# VarmoEmergencyStop_-_Rev_A2.net
KiCad netlist of a schematic drawn in EAGLE
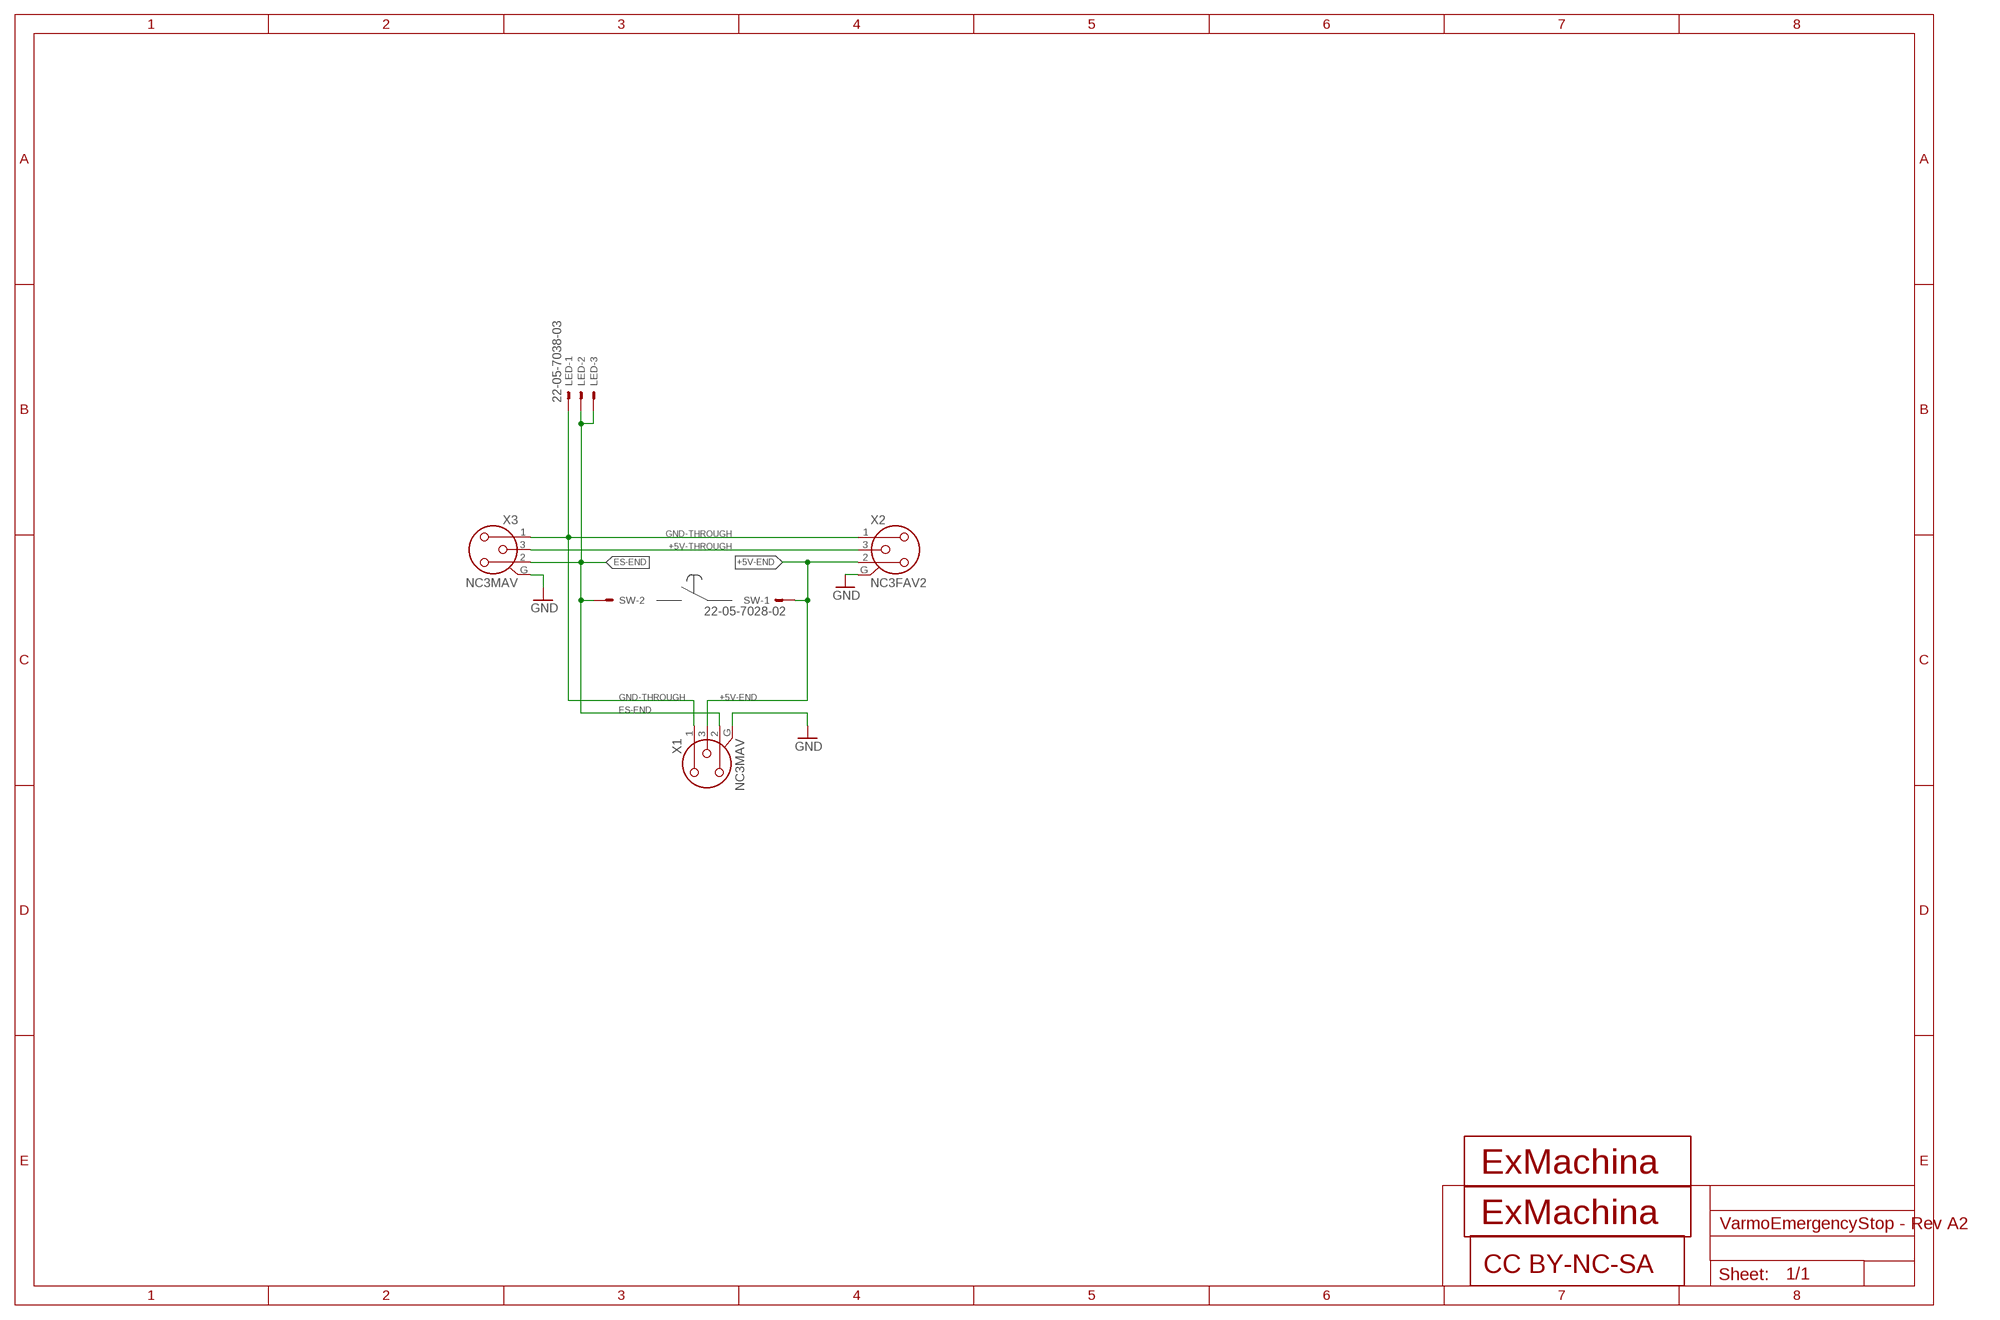
[diagram p0: schematic, sheet 1]

(export (version "E")
  (design (tool "Eeschema 10.0.6"))
  (components
    (comp (ref "LED")
      (value "22-05-7038-03")
      (footprint "eagle-import:7395-03")
      (libsource (lib "eagle-import") (part "22-?-0305-7038"))
    )
    (comp (ref "SW")
      (value "22-05-7028-02")
      (footprint "eagle-import:7395-02")
      (libsource (lib "eagle-import") (part "22-?-0205-7028"))
    )
    (comp (ref "U$1")
      (value "EXMACHINA-LOGO-NAME")
      (footprint "eagle-import:EXM-LOGO-BASELINE")
      (libsource (lib "eagle-import") (part "EXMACHINA-LOGO-NAME"))
    )
    (comp (ref "U$2")
      (value "CC-BY-NC-SA")
      (footprint "eagle-import:CC-BY-NC-SA")
      (libsource (lib "eagle-import") (part "CC-BY-NC-SA"))
    )
    (comp (ref "U$3")
      (value "EXMACHINA-LOGO-NAME")
      (footprint "eagle-import:EXM-LOGO-BASELINE")
      (libsource (lib "eagle-import") (part "EXMACHINA-LOGO-NAME"))
    )
    (comp (ref "X1")
      (value "NC3MAV")
      (footprint "eagle-import:NC3MAV")
      (fields (field (name "MF") "FARNELL"))
      (libsource (lib "eagle-import") (part "NC3MAV"))
    )
    (comp (ref "X2")
      (value "NC3FAV2")
      (footprint "eagle-import:NC3FAV2")
      (fields (field (name "MF") "NEUTRIK"))
      (libsource (lib "eagle-import") (part "NC3FAV2"))
    )
    (comp (ref "X3")
      (value "NC3MAV")
      (footprint "eagle-import:NC3MAV")
      (fields (field (name "MF") "FARNELL"))
      (libsource (lib "eagle-import") (part "NC3MAV"))
    )
  )
  (nets
    (net (code "1") (name "+5V-END") (class "Default")
      (node (ref "SW") (pin "1") (pinfunction "S_1") (pintype "passive"))
      (node (ref "X1") (pin "3") (pinfunction "3_3") (pintype "passive"))
      (node (ref "X2") (pin "2") (pinfunction "2_2") (pintype "passive"))
    )
    (net (code "2") (name "/+5V-THROUGH") (class "Default")
      (node (ref "X2") (pin "3") (pinfunction "3_3") (pintype "passive"))
      (node (ref "X3") (pin "3") (pinfunction "3_3") (pintype "passive"))
    )
    (net (code "3") (name "/GND-THROUGH") (class "Default")
      (node (ref "LED") (pin "1") (pinfunction "S_1") (pintype "passive"))
      (node (ref "X1") (pin "1") (pinfunction "1_1") (pintype "passive"))
      (node (ref "X2") (pin "1") (pinfunction "1_1") (pintype "passive"))
      (node (ref "X3") (pin "1") (pinfunction "1_1") (pintype "passive"))
    )
    (net (code "4") (name "ES-END") (class "Default")
      (node (ref "LED") (pin "2") (pinfunction "S_2") (pintype "passive"))
      (node (ref "LED") (pin "3") (pinfunction "S_3") (pintype "passive"))
      (node (ref "SW") (pin "2") (pinfunction "S_2") (pintype "passive"))
      (node (ref "X1") (pin "2") (pinfunction "2_2") (pintype "passive"))
      (node (ref "X3") (pin "2") (pinfunction "2_2") (pintype "passive"))
    )
    (net (code "5") (name "GND") (class "Default")
      (node (ref "X1") (pin "G") (pinfunction "G_G") (pintype "passive"))
      (node (ref "X2") (pin "G") (pinfunction "G_G") (pintype "passive"))
      (node (ref "X3") (pin "G") (pinfunction "G_G") (pintype "passive"))
    )
  )
)
